# STM32F103RBT6.net
KiCad netlist of a schematic drawn in Altium Designer
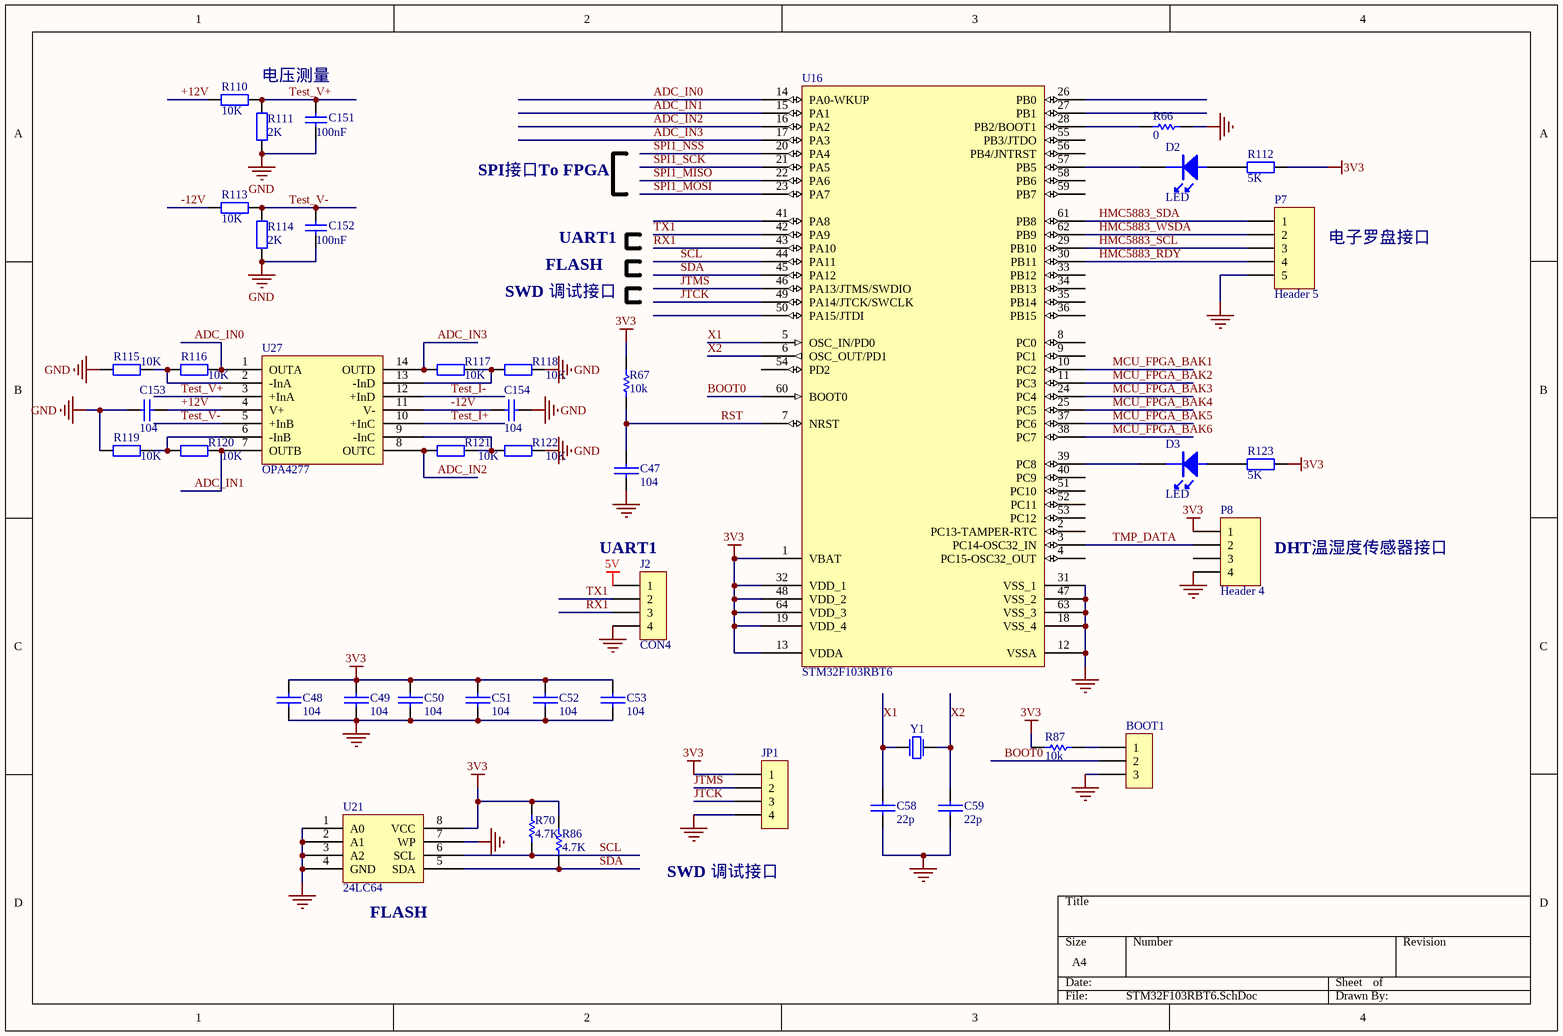
[diagram p0: STM32F103RBT6.SchDoc]

(export (version "E")
  (design (tool "Eeschema 10.0.6"))
  (components
    (comp (ref "BOOT1")
      (value "~")
      (footprint "HDR1X3")
      (description "Connector")
      (libsource (lib "*") (part "CON3"))
    )
    (comp (ref "C47")
      (value "104")
      (footprint "0603")
      (description "Capacitor")
      (libsource (lib "") (part "CAP_1"))
    )
    (comp (ref "C48")
      (value "104")
      (footprint "0603")
      (description "Capacitor")
      (libsource (lib "*") (part "CAP"))
    )
    (comp (ref "C49")
      (value "104")
      (footprint "0603")
      (description "Capacitor")
      (libsource (lib "*") (part "CAP"))
    )
    (comp (ref "C50")
      (value "104")
      (footprint "0603")
      (description "Capacitor")
      (libsource (lib "*") (part "CAP"))
    )
    (comp (ref "C51")
      (value "104")
      (footprint "0603")
      (description "Capacitor")
      (libsource (lib "*") (part "CAP"))
    )
    (comp (ref "C52")
      (value "104")
      (footprint "0603")
      (description "Capacitor")
      (libsource (lib "*") (part "CAP"))
    )
    (comp (ref "C53")
      (value "104")
      (footprint "0603")
      (description "Capacitor")
      (libsource (lib "*") (part "CAP"))
    )
    (comp (ref "C58")
      (value "22p")
      (footprint "0603")
      (description "Capacitor")
      (libsource (lib "*") (part "CAP"))
    )
    (comp (ref "C59")
      (value "22p")
      (footprint "0603")
      (description "Capacitor")
      (libsource (lib "*") (part "CAP"))
    )
    (comp (ref "C151")
      (value "100nF")
      (footprint "0603")
      (description "Capacitor")
      (fields (field (name "Comment") "Cap") (field (name "PUBLISHER") "Altium Limited"))
      (libsource (lib "Miscellaneous Devices") (part "Cap"))
    )
    (comp (ref "C152")
      (value "100nF")
      (footprint "0603")
      (description "Capacitor")
      (fields (field (name "Comment") "Cap") (field (name "PUBLISHER") "Altium Limited"))
      (libsource (lib "Miscellaneous Devices") (part "Cap"))
    )
    (comp (ref "C153")
      (value "104")
      (footprint "0603")
      (description "Capacitor")
      (fields (field (name "PUBLISHER") "Altium Limited"))
      (libsource (lib "Miscellaneous Devices") (part "Cap"))
    )
    (comp (ref "C154")
      (value "104")
      (footprint "0603")
      (description "Capacitor")
      (fields (field (name "PUBLISHER") "Altium Limited"))
      (libsource (lib "Miscellaneous Devices") (part "Cap"))
    )
    (comp (ref "D2") (value "LED") (footprint "0805_LED") (libsource (lib "*") (part "LED")))
    (comp (ref "D3") (value "LED") (footprint "0805_LED") (libsource (lib "*") (part "LED")))
    (comp (ref "J2")
      (value "CON4")
      (footprint "HDR1X4")
      (description "Connector")
      (libsource (lib "*") (part "CON4"))
    )
    (comp (ref "JP1")
      (value "~")
      (footprint "HDR1X4")
      (description "Connector")
      (libsource (lib "*") (part "CON4"))
    )
    (comp (ref "P7")
      (value "Header 5")
      (footprint "HDR1X5")
      (description "Header, 5-Pin")
      (fields (field (name "PUBLISHER") "Altium Limited"))
      (libsource (lib "Miscellaneous Connectors") (part "Header 5"))
    )
    (comp (ref "P8")
      (value "Header 4")
      (footprint "HDR1X4")
      (description "Header, 4-Pin")
      (fields (field (name "PUBLISHER") "Altium Limited"))
      (libsource (lib "Miscellaneous Connectors") (part "Header 4"))
    )
    (comp (ref "R66")
      (value "0")
      (footprint "0603")
      (description "Resistor")
      (fields (field (name "PUBLISHER") "*"))
      (libsource (lib "*") (part "Res1"))
    )
    (comp (ref "R67")
      (value "10k")
      (footprint "0603")
      (description "Resistor")
      (fields (field (name "PUBLISHER") "*"))
      (libsource (lib "*") (part "res1"))
    )
    (comp (ref "R70")
      (value "4.7K")
      (footprint "0603")
      (description "Resistor")
      (fields (field (name "PUBLISHER") "*"))
      (libsource (lib "*") (part "Res1"))
    )
    (comp (ref "R86")
      (value "4.7K")
      (footprint "0603")
      (description "Resistor")
      (fields (field (name "PUBLISHER") "*"))
      (libsource (lib "*") (part "Res1"))
    )
    (comp (ref "R87")
      (value "10k")
      (footprint "0603")
      (description "Resistor")
      (fields (field (name "PUBLISHER") "*"))
      (libsource (lib "*") (part "res1"))
    )
    (comp (ref "R110")
      (value "10K")
      (footprint "0603")
      (description "Resistor")
      (fields (field (name "Comment") "Res2") (field (name "PUBLISHER") "Altium Limited"))
      (libsource (lib "") (part "Res2_2"))
    )
    (comp (ref "R111")
      (value "2K")
      (footprint "0603")
      (description "Resistor")
      (fields (field (name "Comment") "Res2") (field (name "PUBLISHER") "Altium Limited"))
      (libsource (lib "") (part "Res2_1"))
    )
    (comp (ref "R112")
      (value "5K")
      (footprint "0603")
      (description "Resistor")
      (fields (field (name "Comment") "Res2") (field (name "PUBLISHER") "Altium Limited"))
      (libsource (lib "Miscellaneous Devices") (part "Res2"))
    )
    (comp (ref "R113")
      (value "10K")
      (footprint "0603")
      (description "Resistor")
      (fields (field (name "Comment") "Res2") (field (name "PUBLISHER") "Altium Limited"))
      (libsource (lib "") (part "Res2_2"))
    )
    (comp (ref "R114")
      (value "2K")
      (footprint "0603")
      (description "Resistor")
      (fields (field (name "Comment") "Res2") (field (name "PUBLISHER") "Altium Limited"))
      (libsource (lib "") (part "Res2_1"))
    )
    (comp (ref "R115")
      (value "10K")
      (footprint "0603")
      (description "Resistor")
      (fields (field (name "Comment") "Res2") (field (name "PUBLISHER") "Altium Limited"))
      (libsource (lib "Miscellaneous Devices") (part "Res2"))
    )
    (comp (ref "R116")
      (value "10K")
      (footprint "0603")
      (description "Resistor")
      (fields (field (name "Comment") "Res2") (field (name "PUBLISHER") "Altium Limited"))
      (libsource (lib "Miscellaneous Devices") (part "Res2"))
    )
    (comp (ref "R117")
      (value "10K")
      (footprint "0603")
      (description "Resistor")
      (fields (field (name "Comment") "Res2") (field (name "PUBLISHER") "Altium Limited"))
      (libsource (lib "Miscellaneous Devices") (part "Res2"))
    )
    (comp (ref "R118")
      (value "10K")
      (footprint "0603")
      (description "Resistor")
      (fields (field (name "Comment") "Res2") (field (name "PUBLISHER") "Altium Limited"))
      (libsource (lib "Miscellaneous Devices") (part "Res2"))
    )
    (comp (ref "R119")
      (value "10K")
      (footprint "0603")
      (description "Resistor")
      (fields (field (name "Comment") "Res2") (field (name "PUBLISHER") "Altium Limited"))
      (libsource (lib "Miscellaneous Devices") (part "Res2"))
    )
    (comp (ref "R120")
      (value "10K")
      (footprint "0603")
      (description "Resistor")
      (fields (field (name "Comment") "Res2") (field (name "PUBLISHER") "Altium Limited"))
      (libsource (lib "Miscellaneous Devices") (part "Res2"))
    )
    (comp (ref "R121")
      (value "10K")
      (footprint "0603")
      (description "Resistor")
      (fields (field (name "Comment") "Res2") (field (name "PUBLISHER") "Altium Limited"))
      (libsource (lib "Miscellaneous Devices") (part "Res2"))
    )
    (comp (ref "R122")
      (value "10K")
      (footprint "0603")
      (description "Resistor")
      (fields (field (name "Comment") "Res2") (field (name "PUBLISHER") "Altium Limited"))
      (libsource (lib "Miscellaneous Devices") (part "Res2"))
    )
    (comp (ref "R123")
      (value "5K")
      (footprint "0603")
      (description "Resistor")
      (fields (field (name "Comment") "Res2") (field (name "PUBLISHER") "Altium Limited"))
      (libsource (lib "Miscellaneous Devices") (part "Res2"))
    )
    (comp (ref "U16")
      (value "STM32F103RBT6")
      (footprint "LQFP64_M")
      (description "STM32 ARM-based 32-bit MCU with 128 Kbytes Flash, 64-pin LQFP, Industrial Temperature")
      (fields (field (name "PUBLISHER") "*"))
      (libsource (lib "*") (part "STM32F103RBT6"))
    )
    (comp (ref "U21") (value "24LC64") (footprint "SO8") (libsource (lib "*") (part "24C02")))
    (comp (ref "U27") (value "OPA4277") (footprint "SOP14") (libsource (lib "Schlib1") (part "OPA4277")))
    (comp (ref "Y1")
      (value "~")
      (footprint "XTAL_8M")
      (description "Crystal Oscillator")
      (libsource (lib "*") (part "XTAL"))
    )
  )
  (nets
    (net (code "1") (name "/+12V") (class "Default")
      (node (ref "C153") (pin "2") (pinfunction "2_2") (pintype "passive"))
      (node (ref "R110") (pin "2") (pinfunction "2_2") (pintype "passive"))
      (node (ref "U27") (pin "4") (pinfunction "V+_4") (pintype "passive"))
    )
    (net (code "2") (name "/-12V") (class "Default")
      (node (ref "C154") (pin "1") (pinfunction "1_1") (pintype "passive"))
      (node (ref "R113") (pin "2") (pinfunction "2_2") (pintype "passive"))
      (node (ref "U27") (pin "11") (pinfunction "V-_11") (pintype "passive"))
    )
    (net (code "3") (name "/ADC_IN0") (class "Default")
      (node (ref "R116") (pin "2") (pinfunction "2_2") (pintype "passive"))
      (node (ref "U16") (pin "14") (pinfunction "PA0-WKUP_14") (pintype "bidirectional"))
      (node (ref "U27") (pin "1") (pinfunction "OUTA_1") (pintype "passive"))
    )
    (net (code "4") (name "/ADC_IN1") (class "Default")
      (node (ref "R120") (pin "2") (pinfunction "2_2") (pintype "passive"))
      (node (ref "U16") (pin "15") (pinfunction "PA1_15") (pintype "bidirectional"))
      (node (ref "U27") (pin "7") (pinfunction "OUTB_7") (pintype "passive"))
    )
    (net (code "5") (name "/ADC_IN2") (class "Default")
      (node (ref "R121") (pin "1") (pinfunction "1_1") (pintype "passive"))
      (node (ref "U16") (pin "16") (pinfunction "PA2_16") (pintype "bidirectional"))
      (node (ref "U27") (pin "8") (pinfunction "OUTC_8") (pintype "passive"))
    )
    (net (code "6") (name "/ADC_IN3") (class "Default")
      (node (ref "R117") (pin "1") (pinfunction "1_1") (pintype "passive"))
      (node (ref "U16") (pin "17") (pinfunction "PA3_17") (pintype "bidirectional"))
      (node (ref "U27") (pin "14") (pinfunction "OUTD_14") (pintype "passive"))
    )
    (net (code "7") (name "/BOOT0") (class "Default")
      (node (ref "BOOT1") (pin "2") (pinfunction "2_2") (pintype "passive"))
      (node (ref "U16") (pin "60") (pinfunction "BOOT0_60") (pintype "input"))
    )
    (net (code "8") (name "/HMC5883_RDY") (class "Default")
      (node (ref "P7") (pin "4") (pinfunction "4_4") (pintype "passive"))
      (node (ref "U16") (pin "30") (pinfunction "PB11_30") (pintype "bidirectional"))
    )
    (net (code "9") (name "/HMC5883_SCL") (class "Default")
      (node (ref "P7") (pin "3") (pinfunction "3_3") (pintype "passive"))
      (node (ref "U16") (pin "29") (pinfunction "PB10_29") (pintype "bidirectional"))
    )
    (net (code "10") (name "/HMC5883_SDA") (class "Default")
      (node (ref "P7") (pin "1") (pinfunction "1_1") (pintype "passive"))
      (node (ref "U16") (pin "61") (pinfunction "PB8_61") (pintype "bidirectional"))
    )
    (net (code "11") (name "/HMC5883_WSDA") (class "Default")
      (node (ref "P7") (pin "2") (pinfunction "2_2") (pintype "passive"))
      (node (ref "U16") (pin "62") (pinfunction "PB9_62") (pintype "bidirectional"))
    )
    (net (code "12") (name "/JTCK") (class "Default")
      (node (ref "JP1") (pin "3") (pinfunction "3_3") (pintype "passive"))
      (node (ref "U16") (pin "49") (pinfunction "PA14/JTCK/SWCLK_49") (pintype "bidirectional"))
    )
    (net (code "13") (name "/JTMS") (class "Default")
      (node (ref "JP1") (pin "2") (pinfunction "2_2") (pintype "passive"))
      (node (ref "U16") (pin "46") (pinfunction "PA13/JTMS/SWDIO_46") (pintype "bidirectional"))
    )
    (net (code "14") (name "/MCU_FPGA_BAK1") (class "Default")
      (node (ref "U16") (pin "10") (pinfunction "PC2_10") (pintype "bidirectional"))
    )
    (net (code "15") (name "/MCU_FPGA_BAK2") (class "Default")
      (node (ref "U16") (pin "11") (pinfunction "PC3_11") (pintype "bidirectional"))
    )
    (net (code "16") (name "/MCU_FPGA_BAK3") (class "Default")
      (node (ref "U16") (pin "24") (pinfunction "PC4_24") (pintype "bidirectional"))
    )
    (net (code "17") (name "/MCU_FPGA_BAK4") (class "Default")
      (node (ref "U16") (pin "25") (pinfunction "PC5_25") (pintype "bidirectional"))
    )
    (net (code "18") (name "/MCU_FPGA_BAK5") (class "Default")
      (node (ref "U16") (pin "37") (pinfunction "PC6_37") (pintype "bidirectional"))
    )
    (net (code "19") (name "/MCU_FPGA_BAK6") (class "Default")
      (node (ref "U16") (pin "38") (pinfunction "PC7_38") (pintype "bidirectional"))
    )
    (net (code "20") (name "/RST") (class "Default")
      (node (ref "C47") (pin "1") (pinfunction "1_1") (pintype "passive"))
      (node (ref "R67") (pin "1") (pinfunction "1_1") (pintype "passive"))
      (node (ref "U16") (pin "7") (pinfunction "NRST_7") (pintype "bidirectional"))
    )
    (net (code "21") (name "/RX1") (class "Default")
      (node (ref "J2") (pin "3") (pinfunction "3_3") (pintype "passive"))
      (node (ref "U16") (pin "43") (pinfunction "PA10_43") (pintype "bidirectional"))
    )
    (net (code "22") (name "/SCL") (class "Default")
      (node (ref "R70") (pin "1") (pinfunction "1_1") (pintype "passive"))
      (node (ref "U16") (pin "44") (pinfunction "PA11_44") (pintype "bidirectional"))
      (node (ref "U21") (pin "6") (pinfunction "SCL_6") (pintype "passive"))
    )
    (net (code "23") (name "/SDA") (class "Default")
      (node (ref "R86") (pin "1") (pinfunction "1_1") (pintype "passive"))
      (node (ref "U16") (pin "45") (pinfunction "PA12_45") (pintype "bidirectional"))
      (node (ref "U21") (pin "5") (pinfunction "SDA_5") (pintype "passive"))
    )
    (net (code "24") (name "/SPI1_MISO") (class "Default")
      (node (ref "U16") (pin "22") (pinfunction "PA6_22") (pintype "bidirectional"))
    )
    (net (code "25") (name "/SPI1_MOSI") (class "Default")
      (node (ref "U16") (pin "23") (pinfunction "PA7_23") (pintype "bidirectional"))
    )
    (net (code "26") (name "/SPI1_NSS") (class "Default")
      (node (ref "U16") (pin "20") (pinfunction "PA4_20") (pintype "bidirectional"))
    )
    (net (code "27") (name "/SPI1_SCK") (class "Default")
      (node (ref "U16") (pin "21") (pinfunction "PA5_21") (pintype "bidirectional"))
    )
    (net (code "28") (name "/TMP_DATA") (class "Default")
      (node (ref "P8") (pin "2") (pinfunction "2_2") (pintype "passive"))
      (node (ref "U16") (pin "3") (pinfunction "PC14-OSC32_IN_3") (pintype "bidirectional"))
    )
    (net (code "29") (name "/TX1") (class "Default")
      (node (ref "J2") (pin "2") (pinfunction "2_2") (pintype "passive"))
      (node (ref "U16") (pin "42") (pinfunction "PA9_42") (pintype "bidirectional"))
    )
    (net (code "30") (name "/Test_I+") (class "Default")
      (node (ref "U27") (pin "10") (pinfunction "+InC_10") (pintype "passive"))
    )
    (net (code "31") (name "/Test_I-") (class "Default")
      (node (ref "U27") (pin "12") (pinfunction "+InD_12") (pintype "passive"))
    )
    (net (code "32") (name "/Test_V+") (class "Default")
      (node (ref "C151") (pin "2") (pinfunction "2_2") (pintype "passive"))
      (node (ref "R110") (pin "1") (pinfunction "1_1") (pintype "passive"))
      (node (ref "R111") (pin "1") (pinfunction "1_1") (pintype "passive"))
      (node (ref "U27") (pin "3") (pinfunction "+InA_3") (pintype "passive"))
    )
    (net (code "33") (name "/Test_V-") (class "Default")
      (node (ref "C152") (pin "2") (pinfunction "2_2") (pintype "passive"))
      (node (ref "R113") (pin "1") (pinfunction "1_1") (pintype "passive"))
      (node (ref "R114") (pin "1") (pinfunction "1_1") (pintype "passive"))
      (node (ref "U27") (pin "5") (pinfunction "+InB_5") (pintype "passive"))
    )
    (net (code "34") (name "/X1") (class "Default")
      (node (ref "C58") (pin "1") (pinfunction "1_1") (pintype "passive"))
      (node (ref "U16") (pin "5") (pinfunction "OSC_IN/PD0_5") (pintype "input"))
      (node (ref "Y1") (pin "2") (pinfunction "P2_2") (pintype "passive"))
    )
    (net (code "35") (name "/X2") (class "Default")
      (node (ref "C59") (pin "1") (pinfunction "1_1") (pintype "passive"))
      (node (ref "U16") (pin "6") (pinfunction "OSC_OUT/PD1_6") (pintype "output"))
      (node (ref "Y1") (pin "1") (pinfunction "P1_1") (pintype "passive"))
    )
    (net (code "36") (name "3V3") (class "Default")
      (node (ref "C48") (pin "1") (pinfunction "1_1") (pintype "passive"))
      (node (ref "C49") (pin "1") (pinfunction "1_1") (pintype "passive"))
      (node (ref "C50") (pin "1") (pinfunction "1_1") (pintype "passive"))
      (node (ref "C51") (pin "1") (pinfunction "1_1") (pintype "passive"))
      (node (ref "C52") (pin "1") (pinfunction "1_1") (pintype "passive"))
      (node (ref "C53") (pin "1") (pinfunction "1_1") (pintype "passive"))
      (node (ref "JP1") (pin "1") (pinfunction "1_1") (pintype "passive"))
      (node (ref "P8") (pin "1") (pinfunction "1_1") (pintype "passive"))
      (node (ref "R112") (pin "2") (pinfunction "2_2") (pintype "passive"))
      (node (ref "R123") (pin "2") (pinfunction "2_2") (pintype "passive"))
      (node (ref "R67") (pin "2") (pinfunction "2_2") (pintype "passive"))
      (node (ref "R70") (pin "2") (pinfunction "2_2") (pintype "passive"))
      (node (ref "R86") (pin "2") (pinfunction "2_2") (pintype "passive"))
      (node (ref "R87") (pin "1") (pinfunction "1_1") (pintype "passive"))
      (node (ref "U16") (pin "1") (pinfunction "VBAT_1") (pintype "power_in"))
      (node (ref "U16") (pin "13") (pinfunction "VDDA_13") (pintype "power_in"))
      (node (ref "U16") (pin "19") (pinfunction "VDD_4_19") (pintype "power_in"))
      (node (ref "U16") (pin "32") (pinfunction "VDD_1_32") (pintype "power_in"))
      (node (ref "U16") (pin "48") (pinfunction "VDD_2_48") (pintype "power_in"))
      (node (ref "U16") (pin "64") (pinfunction "VDD_3_64") (pintype "power_in"))
      (node (ref "U21") (pin "8") (pinfunction "VCC_8") (pintype "passive"))
    )
    (net (code "37") (name "5V") (class "Default")
      (node (ref "J2") (pin "1") (pinfunction "1_1") (pintype "passive"))
    )
    (net (code "38") (name "GND") (class "Default")
      (node (ref "BOOT1") (pin "3") (pinfunction "3_3") (pintype "passive"))
      (node (ref "C151") (pin "1") (pinfunction "1_1") (pintype "passive"))
      (node (ref "C152") (pin "1") (pinfunction "1_1") (pintype "passive"))
      (node (ref "C153") (pin "1") (pinfunction "1_1") (pintype "passive"))
      (node (ref "C154") (pin "2") (pinfunction "2_2") (pintype "passive"))
      (node (ref "C47") (pin "2") (pinfunction "2_2") (pintype "passive"))
      (node (ref "C48") (pin "2") (pinfunction "2_2") (pintype "passive"))
      (node (ref "C49") (pin "2") (pinfunction "2_2") (pintype "passive"))
      (node (ref "C50") (pin "2") (pinfunction "2_2") (pintype "passive"))
      (node (ref "C51") (pin "2") (pinfunction "2_2") (pintype "passive"))
      (node (ref "C52") (pin "2") (pinfunction "2_2") (pintype "passive"))
      (node (ref "C53") (pin "2") (pinfunction "2_2") (pintype "passive"))
      (node (ref "C58") (pin "2") (pinfunction "2_2") (pintype "passive"))
      (node (ref "C59") (pin "2") (pinfunction "2_2") (pintype "passive"))
      (node (ref "J2") (pin "4") (pinfunction "4_4") (pintype "passive"))
      (node (ref "JP1") (pin "4") (pinfunction "4_4") (pintype "passive"))
      (node (ref "P7") (pin "5") (pinfunction "5_5") (pintype "passive"))
      (node (ref "P8") (pin "4") (pinfunction "4_4") (pintype "passive"))
      (node (ref "R111") (pin "2") (pinfunction "2_2") (pintype "passive"))
      (node (ref "R114") (pin "2") (pinfunction "2_2") (pintype "passive"))
      (node (ref "R115") (pin "1") (pinfunction "1_1") (pintype "passive"))
      (node (ref "R118") (pin "2") (pinfunction "2_2") (pintype "passive"))
      (node (ref "R119") (pin "1") (pinfunction "1_1") (pintype "passive"))
      (node (ref "R122") (pin "2") (pinfunction "2_2") (pintype "passive"))
      (node (ref "R66") (pin "2") (pinfunction "2_2") (pintype "passive"))
      (node (ref "U16") (pin "12") (pinfunction "VSSA_12") (pintype "power_in"))
      (node (ref "U16") (pin "18") (pinfunction "VSS_4_18") (pintype "power_in"))
      (node (ref "U16") (pin "31") (pinfunction "VSS_1_31") (pintype "power_in"))
      (node (ref "U16") (pin "47") (pinfunction "VSS_2_47") (pintype "power_in"))
      (node (ref "U16") (pin "63") (pinfunction "VSS_3_63") (pintype "power_in"))
      (node (ref "U21") (pin "1") (pinfunction "A0_1") (pintype "passive"))
      (node (ref "U21") (pin "2") (pinfunction "A1_2") (pintype "passive"))
      (node (ref "U21") (pin "3") (pinfunction "A2_3") (pintype "passive"))
      (node (ref "U21") (pin "4") (pinfunction "GND_4") (pintype "passive"))
      (node (ref "U21") (pin "7") (pinfunction "WP_7") (pintype "passive"))
    )
    (net (code "39") (name "Net-(BOOT1-Pad1)") (class "Default")
      (node (ref "BOOT1") (pin "1") (pinfunction "1_1") (pintype "passive"))
      (node (ref "R87") (pin "2") (pinfunction "2_2") (pintype "passive"))
    )
    (net (code "40") (name "Net-(D2-A)") (class "Default")
      (node (ref "D2") (pin "1") (pinfunction "A_1") (pintype "passive"))
      (node (ref "R112") (pin "1") (pinfunction "1_1") (pintype "passive"))
    )
    (net (code "41") (name "Net-(D2-K)") (class "Default")
      (node (ref "D2") (pin "2") (pinfunction "K_2") (pintype "passive"))
      (node (ref "U16") (pin "57") (pinfunction "PB5_57") (pintype "bidirectional"))
    )
    (net (code "42") (name "Net-(D3-A)") (class "Default")
      (node (ref "D3") (pin "1") (pinfunction "A_1") (pintype "passive"))
      (node (ref "R123") (pin "1") (pinfunction "1_1") (pintype "passive"))
    )
    (net (code "43") (name "Net-(D3-K)") (class "Default")
      (node (ref "D3") (pin "2") (pinfunction "K_2") (pintype "passive"))
      (node (ref "U16") (pin "39") (pinfunction "PC8_39") (pintype "bidirectional"))
    )
    (net (code "44") (name "Net-(U16-PB2{slash}BOOT1)") (class "Default")
      (node (ref "R66") (pin "1") (pinfunction "1_1") (pintype "passive"))
      (node (ref "U16") (pin "28") (pinfunction "PB2/BOOT1_28") (pintype "bidirectional"))
    )
    (net (code "45") (name "Net-(U27--InA)") (class "Default")
      (node (ref "R115") (pin "2") (pinfunction "2_2") (pintype "passive"))
      (node (ref "R116") (pin "1") (pinfunction "1_1") (pintype "passive"))
      (node (ref "U27") (pin "2") (pinfunction "-InA_2") (pintype "passive"))
    )
    (net (code "46") (name "Net-(U27--InB)") (class "Default")
      (node (ref "R119") (pin "2") (pinfunction "2_2") (pintype "passive"))
      (node (ref "R120") (pin "1") (pinfunction "1_1") (pintype "passive"))
      (node (ref "U27") (pin "6") (pinfunction "-InB_6") (pintype "passive"))
    )
    (net (code "47") (name "Net-(U27--InC)") (class "Default")
      (node (ref "R121") (pin "2") (pinfunction "2_2") (pintype "passive"))
      (node (ref "R122") (pin "1") (pinfunction "1_1") (pintype "passive"))
      (node (ref "U27") (pin "9") (pinfunction "-InC_9") (pintype "passive"))
    )
    (net (code "48") (name "Net-(U27--InD)") (class "Default")
      (node (ref "R117") (pin "2") (pinfunction "2_2") (pintype "passive"))
      (node (ref "R118") (pin "1") (pinfunction "1_1") (pintype "passive"))
      (node (ref "U27") (pin "13") (pinfunction "-InD_13") (pintype "passive"))
    )
    (net (code "49") (name "unconnected-(P8-Pad3)") (class "Default")
      (node (ref "P8") (pin "3") (pinfunction "3_3") (pintype "passive"))
    )
    (net (code "50") (name "unconnected-(U16-PA8-Pad41)") (class "Default")
      (node (ref "U16") (pin "41") (pinfunction "PA8_41") (pintype "bidirectional"))
    )
    (net (code "51") (name "unconnected-(U16-PA15{slash}JTDI-Pad50)") (class "Default")
      (node (ref "U16") (pin "50") (pinfunction "PA15/JTDI_50") (pintype "bidirectional"))
    )
    (net (code "52") (name "unconnected-(U16-PB0-Pad26)") (class "Default")
      (node (ref "U16") (pin "26") (pinfunction "PB0_26") (pintype "bidirectional"))
    )
    (net (code "53") (name "unconnected-(U16-PB1-Pad27)") (class "Default")
      (node (ref "U16") (pin "27") (pinfunction "PB1_27") (pintype "bidirectional"))
    )
    (net (code "54") (name "unconnected-(U16-PB3{slash}JTDO-Pad55)") (class "Default")
      (node (ref "U16") (pin "55") (pinfunction "PB3/JTDO_55") (pintype "bidirectional"))
    )
    (net (code "55") (name "unconnected-(U16-PB4{slash}JNTRST-Pad56)") (class "Default")
      (node (ref "U16") (pin "56") (pinfunction "PB4/JNTRST_56") (pintype "bidirectional"))
    )
    (net (code "56") (name "unconnected-(U16-PB6-Pad58)") (class "Default")
      (node (ref "U16") (pin "58") (pinfunction "PB6_58") (pintype "bidirectional"))
    )
    (net (code "57") (name "unconnected-(U16-PB7-Pad59)") (class "Default")
      (node (ref "U16") (pin "59") (pinfunction "PB7_59") (pintype "bidirectional"))
    )
    (net (code "58") (name "unconnected-(U16-PB12-Pad33)") (class "Default")
      (node (ref "U16") (pin "33") (pinfunction "PB12_33") (pintype "bidirectional"))
    )
    (net (code "59") (name "unconnected-(U16-PB13-Pad34)") (class "Default")
      (node (ref "U16") (pin "34") (pinfunction "PB13_34") (pintype "bidirectional"))
    )
    (net (code "60") (name "unconnected-(U16-PB14-Pad35)") (class "Default")
      (node (ref "U16") (pin "35") (pinfunction "PB14_35") (pintype "bidirectional"))
    )
    (net (code "61") (name "unconnected-(U16-PB15-Pad36)") (class "Default")
      (node (ref "U16") (pin "36") (pinfunction "PB15_36") (pintype "bidirectional"))
    )
    (net (code "62") (name "unconnected-(U16-PC0-Pad8)") (class "Default")
      (node (ref "U16") (pin "8") (pinfunction "PC0_8") (pintype "bidirectional"))
    )
    (net (code "63") (name "unconnected-(U16-PC1-Pad9)") (class "Default")
      (node (ref "U16") (pin "9") (pinfunction "PC1_9") (pintype "bidirectional"))
    )
    (net (code "64") (name "unconnected-(U16-PC9-Pad40)") (class "Default")
      (node (ref "U16") (pin "40") (pinfunction "PC9_40") (pintype "bidirectional"))
    )
    (net (code "65") (name "unconnected-(U16-PC10-Pad51)") (class "Default")
      (node (ref "U16") (pin "51") (pinfunction "PC10_51") (pintype "bidirectional"))
    )
    (net (code "66") (name "unconnected-(U16-PC11-Pad52)") (class "Default")
      (node (ref "U16") (pin "52") (pinfunction "PC11_52") (pintype "bidirectional"))
    )
    (net (code "67") (name "unconnected-(U16-PC12-Pad53)") (class "Default")
      (node (ref "U16") (pin "53") (pinfunction "PC12_53") (pintype "bidirectional"))
    )
    (net (code "68") (name "unconnected-(U16-PC13-TAMPER-RTC-Pad2)") (class "Default")
      (node (ref "U16") (pin "2") (pinfunction "PC13-TAMPER-RTC_2") (pintype "bidirectional"))
    )
    (net (code "69") (name "unconnected-(U16-PC15-OSC32_OUT-Pad4)") (class "Default")
      (node (ref "U16") (pin "4") (pinfunction "PC15-OSC32_OUT_4") (pintype "bidirectional"))
    )
    (net (code "70") (name "unconnected-(U16-PD2-Pad54)") (class "Default")
      (node (ref "U16") (pin "54") (pinfunction "PD2_54") (pintype "bidirectional"))
    )
  )
)
